# BatDuino1_0.net
KiCad netlist of a schematic drawn in EAGLE
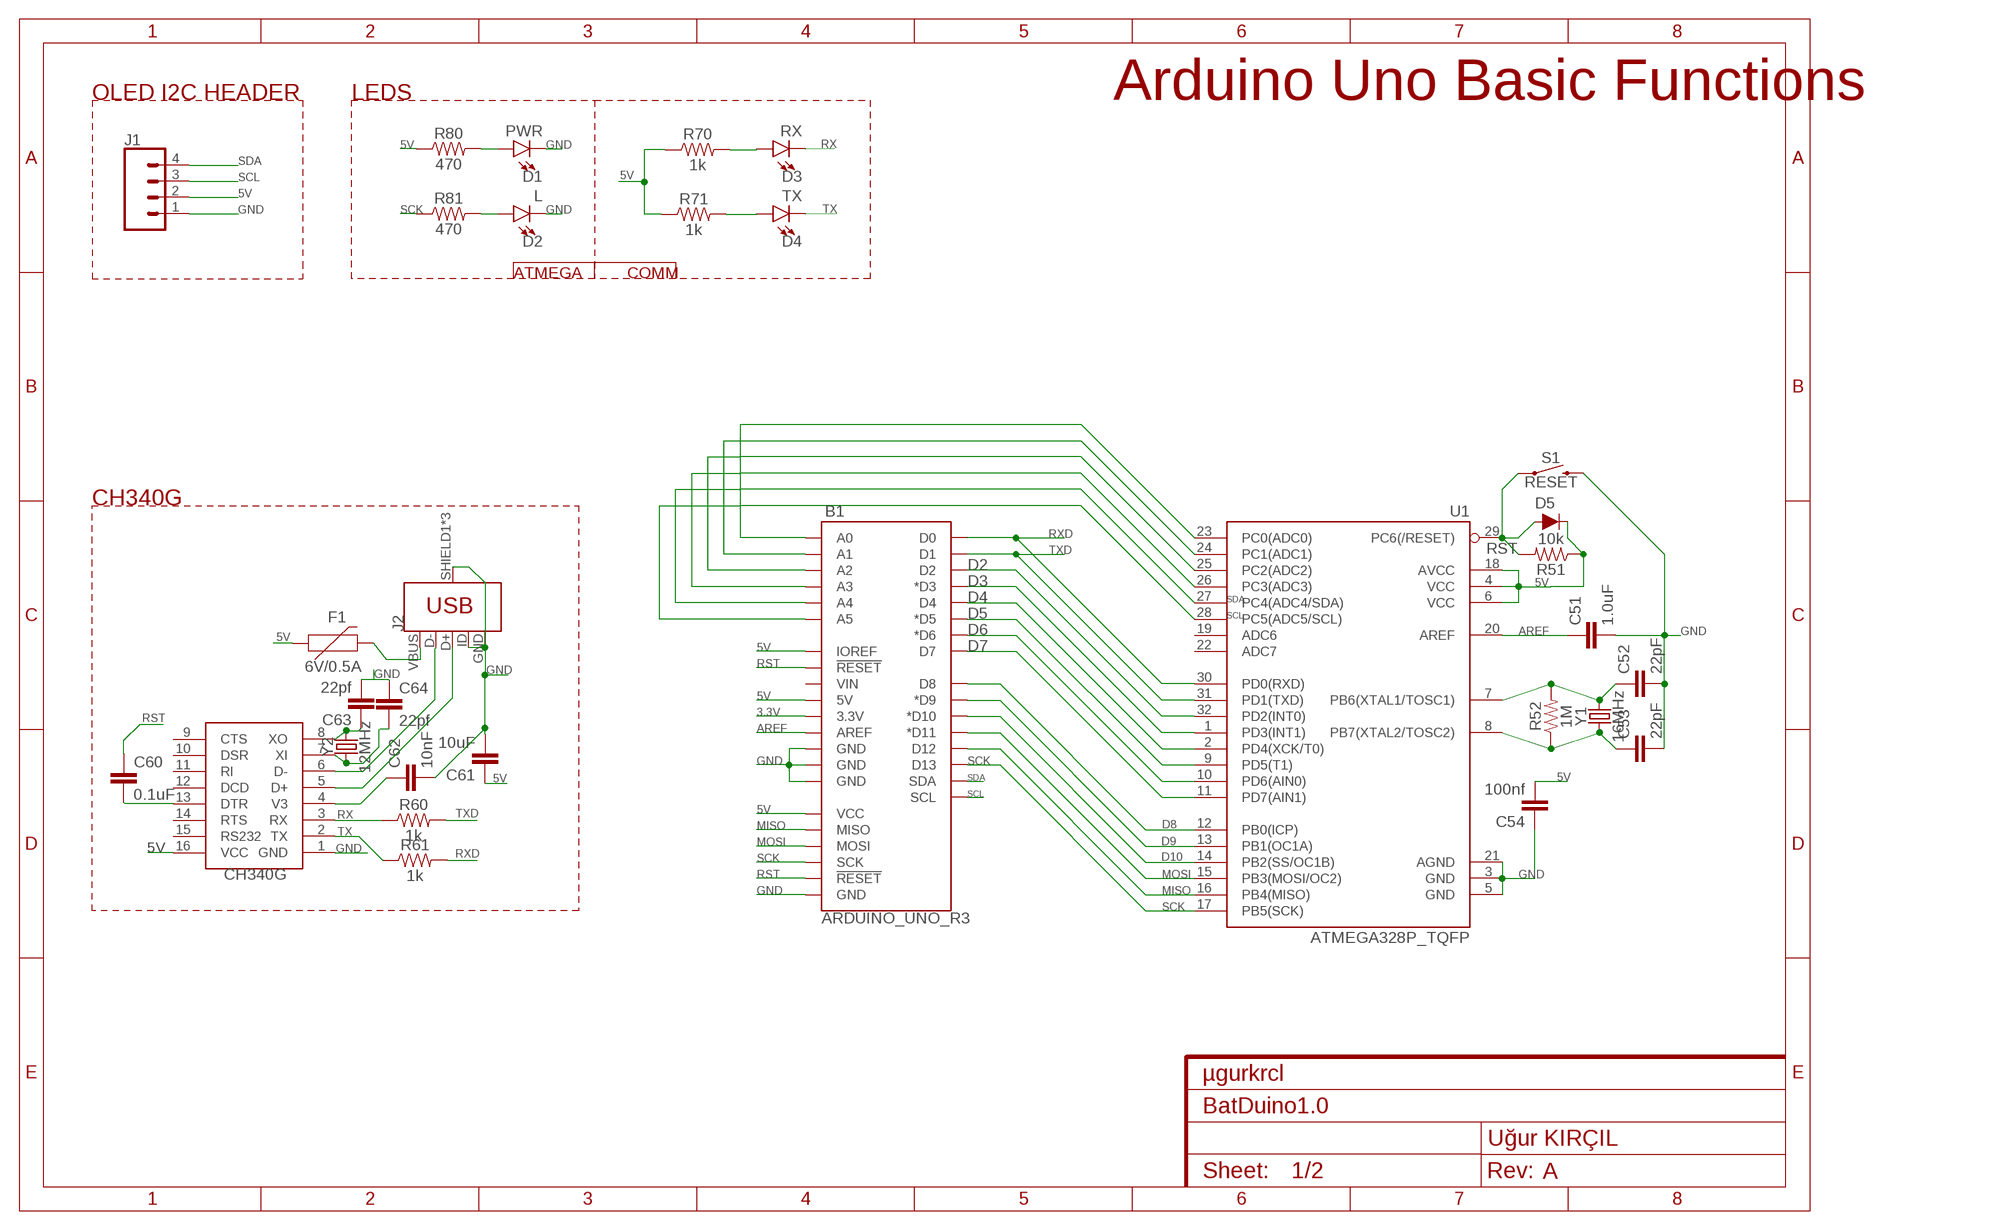
[diagram p0: schematic, sheet 1]
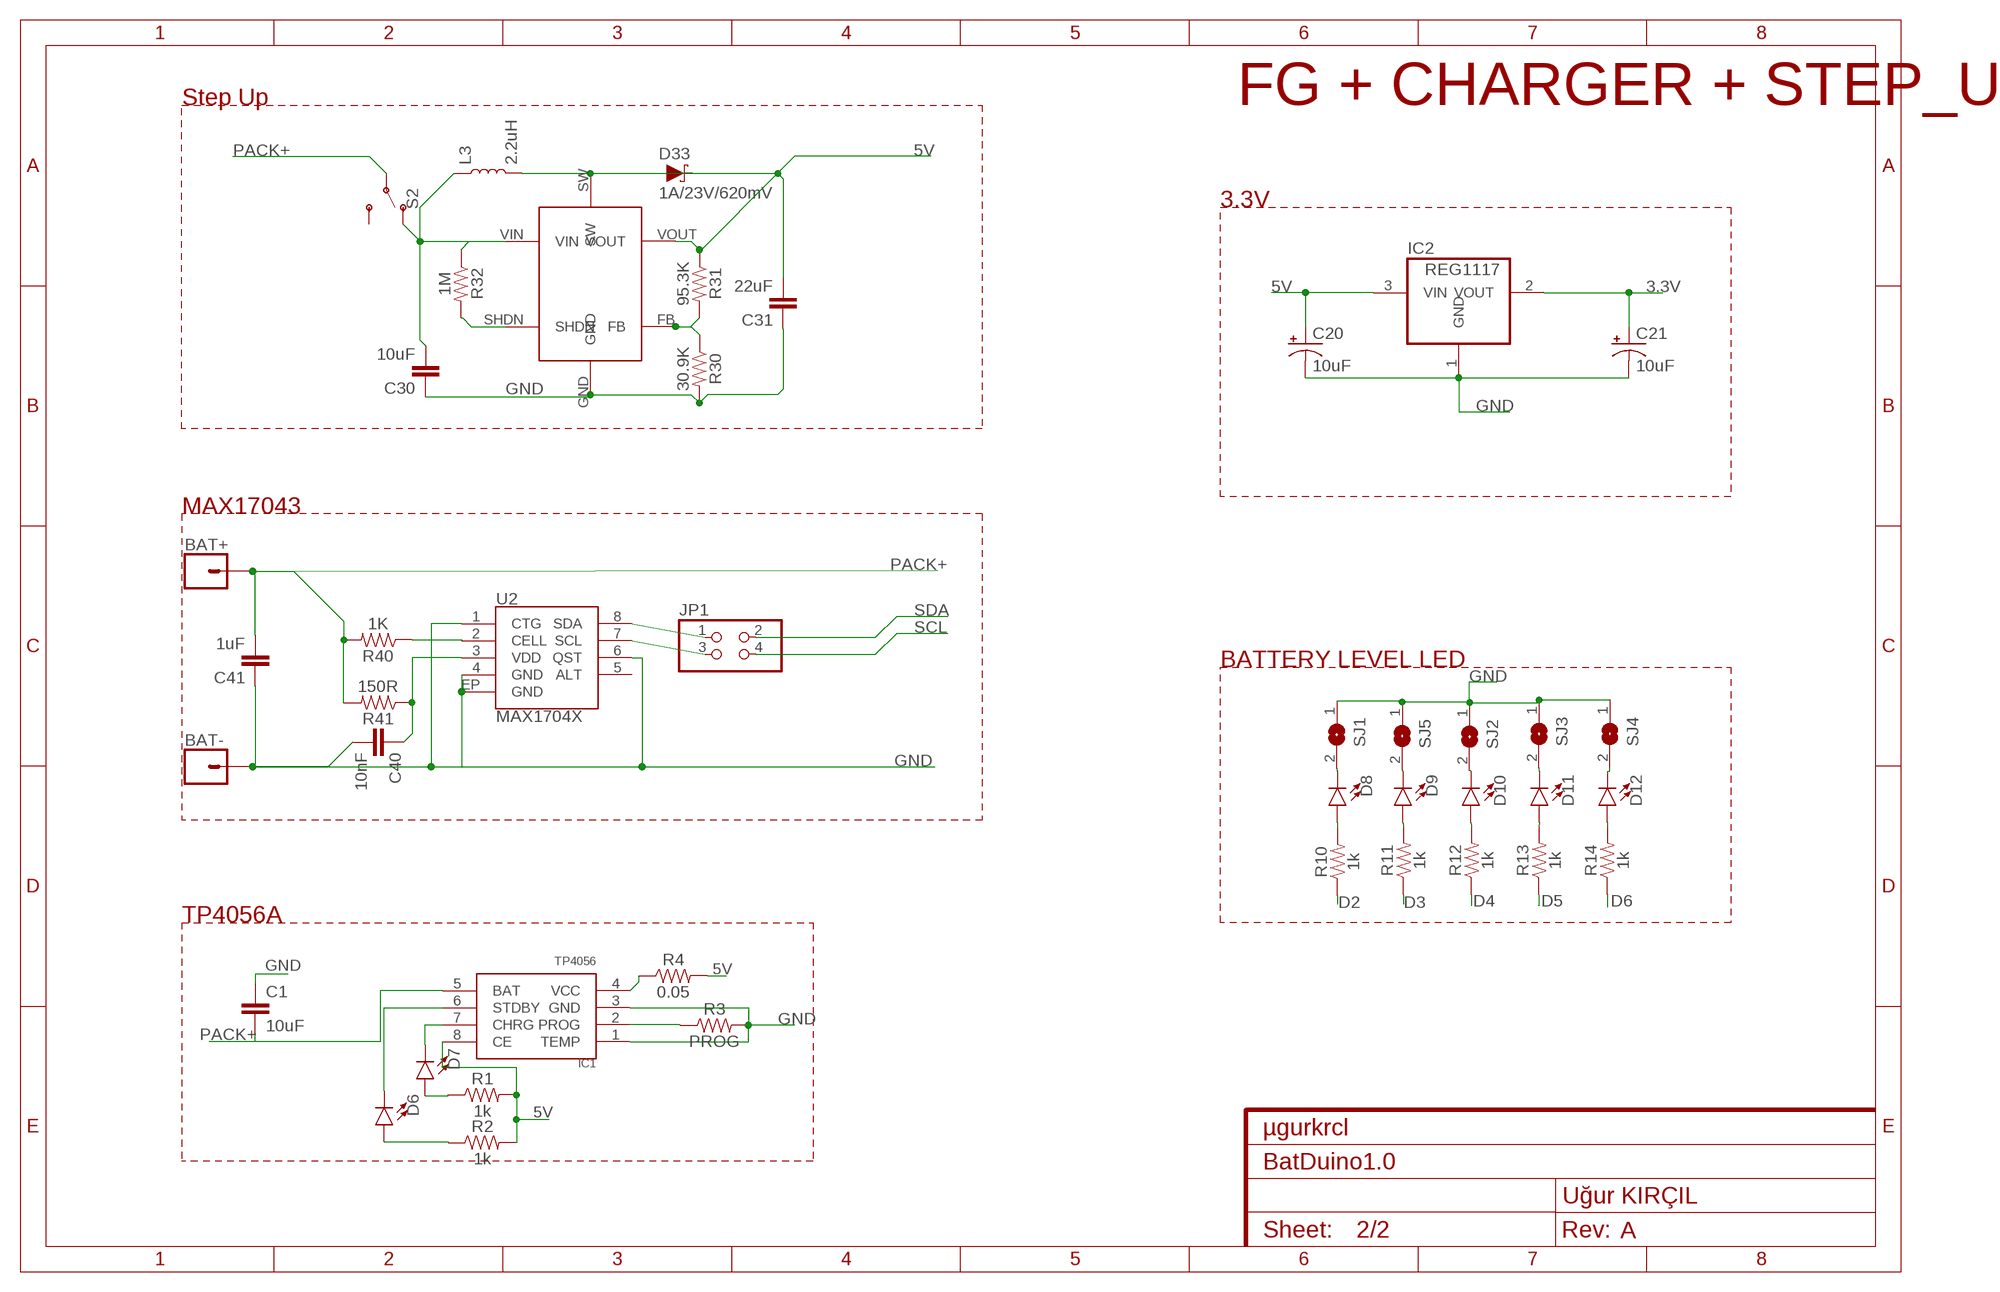
[diagram p1: schematic, sheet 2]

(export (version "E")
  (design (tool "Eeschema 10.0.6"))
  (components
    (comp (ref "B1")
      (value "ARDUINO_UNO_R3")
      (footprint "eagle-import:ARDUINO_R3")
      (libsource (lib "eagle-import") (part "ARDUINO_UNO_R3"))
    )
    (comp (ref "C51")
      (value "1.0uF")
      (footprint "eagle-import:0603")
      (libsource (lib "eagle-import") (part "1.0UF-0603-16V-10%"))
    )
    (comp (ref "C52")
      (value "22pF")
      (footprint "eagle-import:0603")
      (libsource (lib "eagle-import") (part "22PF-0603-50V-5%"))
    )
    (comp (ref "C53")
      (value "22pF")
      (footprint "eagle-import:0603")
      (libsource (lib "eagle-import") (part "22PF-0603-50V-5%"))
    )
    (comp (ref "C54")
      (value "100nf")
      (footprint "eagle-import:0603")
      (libsource (lib "eagle-import") (part "22PF-0603-50V-5%"))
    )
    (comp (ref "C60")
      (value "0.1uF")
      (footprint "eagle-import:0603")
      (libsource (lib "eagle-import") (part "0.1UF-0603-25V-5%"))
    )
    (comp (ref "C61")
      (value "10uF")
      (footprint "eagle-import:0603")
      (libsource (lib "eagle-import") (part "0.18UF-0603-10V-10%"))
    )
    (comp (ref "C62")
      (value "10nF")
      (footprint "eagle-import:0603")
      (libsource (lib "eagle-import") (part "0.18UF-0603-10V-10%"))
    )
    (comp (ref "C63")
      (value "22pf")
      (footprint "eagle-import:0603")
      (libsource (lib "eagle-import") (part "0.18UF-0603-10V-10%"))
    )
    (comp (ref "C64")
      (value "22pf")
      (footprint "eagle-import:0603")
      (libsource (lib "eagle-import") (part "0.18UF-0603-10V-10%"))
    )
    (comp (ref "D1")
      (value "PWR")
      (footprint "eagle-import:LED-0603")
      (libsource (lib "eagle-import") (part "LED-GREEN0603"))
    )
    (comp (ref "D2")
      (value "L")
      (footprint "eagle-import:LED-0603")
      (libsource (lib "eagle-import") (part "LED-GREEN0603"))
    )
    (comp (ref "D3")
      (value "RX")
      (footprint "eagle-import:LED-0603")
      (libsource (lib "eagle-import") (part "LED-GREEN0603"))
    )
    (comp (ref "D4")
      (value "TX")
      (footprint "eagle-import:LED-0603")
      (libsource (lib "eagle-import") (part "LED-GREEN0603"))
    )
    (comp (ref "D5")
      (value "DIODE-BAS16J")
      (footprint "eagle-import:SOD-323")
      (libsource (lib "eagle-import") (part "DIODE-BAS16J"))
    )
    (comp (ref "F1")
      (value "6V/0.5A")
      (footprint "eagle-import:1206")
      (libsource (lib "eagle-import") (part "PPTC_HALF-AMP"))
    )
    (comp (ref "J1")
      (value "CONN_04")
      (footprint "eagle-import:1X04")
      (libsource (lib "eagle-import") (part "CONN_04"))
    )
    (comp (ref "J2")
      (value "USB_MICRO-BREDUCED_PASTE")
      (footprint "eagle-import:USB-B-MICRO-SMD_RED_PASTE")
      (libsource (lib "eagle-import") (part "USB_MICRO-BREDUCED_PASTE"))
    )
    (comp (ref "R51")
      (value "10k")
      (footprint "eagle-import:0603")
      (libsource (lib "eagle-import") (part "10KOHM-0603-1/10W-1%"))
    )
    (comp (ref "R52")
      (value "1M")
      (footprint "eagle-import:0603")
      (libsource (lib "eagle-import") (part "1MOHM-0603-1/4W-5%"))
    )
    (comp (ref "R60")
      (value "1k")
      (footprint "eagle-import:0603")
      (libsource (lib "eagle-import") (part "1KOHM-0603-1/10W-1%"))
    )
    (comp (ref "R61")
      (value "1k")
      (footprint "eagle-import:0603")
      (libsource (lib "eagle-import") (part "1KOHM-0603-1/10W-1%"))
    )
    (comp (ref "R70")
      (value "1k")
      (footprint "eagle-import:0603")
      (libsource (lib "eagle-import") (part "1KOHM-0603-1/10W-1%"))
    )
    (comp (ref "R71")
      (value "1k")
      (footprint "eagle-import:0603")
      (libsource (lib "eagle-import") (part "1KOHM-0603-1/10W-1%"))
    )
    (comp (ref "R80")
      (value "470")
      (footprint "eagle-import:0603")
      (libsource (lib "eagle-import") (part "470OHM-0603-1/10W-1%"))
    )
    (comp (ref "R81")
      (value "470")
      (footprint "eagle-import:0603")
      (libsource (lib "eagle-import") (part "470OHM-0603-1/10W-1%"))
    )
    (comp (ref "S1")
      (value "RESET")
      (footprint "eagle-import:TACTILE_SWITCH_PTH_6.0MM")
      (libsource (lib "eagle-import") (part "MOMENTARY-SWITCH-SPST-PTH-6.0MM"))
    )
    (comp (ref "U$1")
      (value "CH340G")
      (footprint "eagle-import:SOIC16")
      (libsource (lib "eagle-import") (part "CH340G"))
    )
    (comp (ref "U1")
      (value "ATMEGA328P_TQFP")
      (footprint "eagle-import:TQFP32-08")
      (libsource (lib "eagle-import") (part "ATMEGA328P_TQFP"))
    )
    (comp (ref "Y1")
      (value "16MHz")
      (footprint "eagle-import:HC49US")
      (libsource (lib "eagle-import") (part "CRYSTAL-16MHZPTH-HC49US"))
    )
    (comp (ref "Y2")
      (value "12MHz")
      (footprint "eagle-import:HC49US")
      (libsource (lib "eagle-import") (part "CRYSTAL-16MHZPTH-HC49US"))
    )
    (comp (ref "BAT+")
      (value "CONN_01")
      (footprint "eagle-import:1X01")
      (libsource (lib "eagle-import") (part "CONN_01"))
    )
    (comp (ref "BAT-")
      (value "CONN_01")
      (footprint "eagle-import:1X01")
      (libsource (lib "eagle-import") (part "CONN_01"))
    )
    (comp (ref "C1")
      (value "10uF")
      (footprint "eagle-import:0603")
      (libsource (lib "eagle-import") (part "10UF-0603-6.3V-20%"))
    )
    (comp (ref "C20")
      (value "10uF")
      (footprint "eagle-import:EIA3528")
      (libsource (lib "eagle-import") (part "10UF-POLAR-EIA3528-20V-10%(TANT)"))
    )
    (comp (ref "C21")
      (value "10uF")
      (footprint "eagle-import:EIA3528")
      (libsource (lib "eagle-import") (part "10UF-POLAR-EIA3528-20V-10%(TANT)"))
    )
    (comp (ref "C30")
      (value "10uF")
      (footprint "eagle-import:0603")
      (libsource (lib "eagle-import") (part "0.1UF-0603-25V-(+80/-20%)"))
    )
    (comp (ref "C31")
      (value "22uF")
      (footprint "eagle-import:0603")
      (libsource (lib "eagle-import") (part "0.1UF-0603-25V-(+80/-20%)"))
    )
    (comp (ref "C40")
      (value "10nF")
      (footprint "eagle-import:0603")
      (libsource (lib "eagle-import") (part "0.1UF-0603-25V-(+80/-20%)"))
    )
    (comp (ref "C41")
      (value "1uF")
      (footprint "eagle-import:0603")
      (libsource (lib "eagle-import") (part "0.1UF-0603-25V-(+80/-20%)"))
    )
    (comp (ref "D6")
      (value "LED0603")
      (footprint "eagle-import:LED-0603")
      (libsource (lib "eagle-import") (part "LED0603"))
    )
    (comp (ref "D7")
      (value "LED0603")
      (footprint "eagle-import:LED-0603")
      (libsource (lib "eagle-import") (part "LED0603"))
    )
    (comp (ref "D8")
      (value "LED0603")
      (footprint "eagle-import:LED-0603")
      (libsource (lib "eagle-import") (part "LED0603"))
    )
    (comp (ref "D9")
      (value "LED0603")
      (footprint "eagle-import:LED-0603")
      (libsource (lib "eagle-import") (part "LED0603"))
    )
    (comp (ref "D10")
      (value "LED0603")
      (footprint "eagle-import:LED-0603")
      (libsource (lib "eagle-import") (part "LED0603"))
    )
    (comp (ref "D11")
      (value "LED0603")
      (footprint "eagle-import:LED-0603")
      (libsource (lib "eagle-import") (part "LED0603"))
    )
    (comp (ref "D12")
      (value "LED0603")
      (footprint "eagle-import:LED-0603")
      (libsource (lib "eagle-import") (part "LED0603"))
    )
    (comp (ref "D33")
      (value "1A/23V/620mV")
      (footprint "eagle-import:SOD-323")
      (libsource (lib "eagle-import") (part "DIODE-SCHOTTKY-BAT20J"))
    )
    (comp (ref "IC1")
      (value "TP4056")
      (footprint "eagle-import:SOP-8")
      (libsource (lib "eagle-import") (part "TP4056"))
    )
    (comp (ref "IC2")
      (value "REG1117")
      (footprint "eagle-import:SOT223")
      (libsource (lib "eagle-import") (part "REG1117"))
    )
    (comp (ref "JP1")
      (value "PINHD-2X2")
      (footprint "eagle-import:2X02")
      (libsource (lib "eagle-import") (part "PINHD-2X2"))
    )
    (comp (ref "L3")
      (value "2.2uH")
      (footprint "eagle-import:INDUCTOR_4.7UH")
      (libsource (lib "eagle-import") (part "INDUCTOR-CDRH-4.7UH"))
    )
    (comp (ref "R1")
      (value "1k")
      (footprint "eagle-import:0603")
      (libsource (lib "eagle-import") (part "1KOHM-0603-1/10W-1%"))
    )
    (comp (ref "R2")
      (value "1k")
      (footprint "eagle-import:0603")
      (libsource (lib "eagle-import") (part "1KOHM-0603-1/10W-1%"))
    )
    (comp (ref "R3")
      (value "PROG")
      (footprint "eagle-import:AXIAL-0.3")
      (libsource (lib "eagle-import") (part "1KOHM-HORIZ-1/4W-1%"))
    )
    (comp (ref "R4")
      (value "0.05")
      (footprint "eagle-import:0603")
      (libsource (lib "eagle-import") (part "0.05OHM-0603-1/5W-1%"))
    )
    (comp (ref "R10")
      (value "1k")
      (footprint "eagle-import:0603")
      (libsource (lib "eagle-import") (part "1KOHM-0603-1/10W-1%"))
    )
    (comp (ref "R11")
      (value "1k")
      (footprint "eagle-import:0603")
      (libsource (lib "eagle-import") (part "1KOHM-0603-1/10W-1%"))
    )
    (comp (ref "R12")
      (value "1k")
      (footprint "eagle-import:0603")
      (libsource (lib "eagle-import") (part "1KOHM-0603-1/10W-1%"))
    )
    (comp (ref "R13")
      (value "1k")
      (footprint "eagle-import:0603")
      (libsource (lib "eagle-import") (part "1KOHM-0603-1/10W-1%"))
    )
    (comp (ref "R14")
      (value "1k")
      (footprint "eagle-import:0603")
      (libsource (lib "eagle-import") (part "1KOHM-0603-1/10W-1%"))
    )
    (comp (ref "R30")
      (value "30.9K")
      (footprint "eagle-import:0603")
      (libsource (lib "eagle-import") (part "0.05OHM-0603-1/5W-1%"))
    )
    (comp (ref "R31")
      (value "95.3K")
      (footprint "eagle-import:0603")
      (libsource (lib "eagle-import") (part "0.05OHM-0603-1/5W-1%"))
    )
    (comp (ref "R32")
      (value "1M")
      (footprint "eagle-import:0603")
      (libsource (lib "eagle-import") (part "0.05OHM-0603-1/5W-1%"))
    )
    (comp (ref "R40")
      (value "1K")
      (footprint "eagle-import:0603")
      (libsource (lib "eagle-import") (part "0.05OHM-0603-1/5W-1%"))
    )
    (comp (ref "R41")
      (value "150R")
      (footprint "eagle-import:0603")
      (libsource (lib "eagle-import") (part "0.05OHM-0603-1/5W-1%"))
    )
    (comp (ref "S2")
      (value "SWITCH-SPDT-SMD-RIGHT-ANGLE")
      (footprint "eagle-import:SWITCH_SPST_SMD_A")
      (libsource (lib "eagle-import") (part "SWITCH-SPDT-SMD-RIGHT-ANGLE"))
    )
    (comp (ref "SJ1") (value "SJ") (footprint "eagle-import:SJ") (libsource (lib "eagle-import") (part "SJ")))
    (comp (ref "SJ2") (value "SJ") (footprint "eagle-import:SJ") (libsource (lib "eagle-import") (part "SJ")))
    (comp (ref "SJ3") (value "SJ") (footprint "eagle-import:SJ") (libsource (lib "eagle-import") (part "SJ")))
    (comp (ref "SJ4") (value "SJ") (footprint "eagle-import:SJ") (libsource (lib "eagle-import") (part "SJ")))
    (comp (ref "SJ5") (value "SJ") (footprint "eagle-import:SJ") (libsource (lib "eagle-import") (part "SJ")))
    (comp (ref "U$2")
      (value "XR1151")
      (footprint "eagle-import:SOT23-6")
      (libsource (lib "eagle-import") (part "XR1151"))
    )
    (comp (ref "U2")
      (value "MAX1704X")
      (footprint "eagle-import:TDFN-8")
      (libsource (lib "eagle-import") (part "MAX1704X"))
    )
  )
  (nets
    (net (code "1") (name "3.3V") (class "Default")
      (node (ref "B1") (pin "3.3V") (pinfunction "3.3V_3.3V") (pintype "bidirectional"))
      (node (ref "C21") (pin "A") (pinfunction "+_A") (pintype "passive"))
      (node (ref "IC2") (pin "2") (pinfunction "VOUT_2") (pintype "output"))
    )
    (net (code "2") (name "5V") (class "Default")
      (node (ref "B1") (pin "5V") (pinfunction "5V_5V") (pintype "bidirectional"))
      (node (ref "B1") (pin "IOREF") (pinfunction "IOREF_IOREF") (pintype "bidirectional"))
      (node (ref "B1") (pin "VCC") (pinfunction "VCC_VCC") (pintype "bidirectional"))
      (node (ref "C20") (pin "A") (pinfunction "+_A") (pintype "passive"))
      (node (ref "C31") (pin "2") (pinfunction "2_2") (pintype "passive"))
      (node (ref "C54") (pin "2") (pinfunction "2_2") (pintype "passive"))
      (node (ref "C61") (pin "1") (pinfunction "1_1") (pintype "passive"))
      (node (ref "D33") (pin "A") (pinfunction "A_A") (pintype "passive"))
      (node (ref "D5") (pin "C") (pinfunction "C_C") (pintype "passive"))
      (node (ref "F1") (pin "1") (pinfunction "1_1") (pintype "bidirectional"))
      (node (ref "IC1") (pin "8") (pinfunction "CE_8") (pintype "bidirectional"))
      (node (ref "IC2") (pin "3") (pinfunction "VIN_3") (pintype "input"))
      (node (ref "J1") (pin "2") (pinfunction "2_2") (pintype "passive"))
      (node (ref "R1") (pin "2") (pinfunction "2_2") (pintype "passive"))
      (node (ref "R2") (pin "2") (pinfunction "2_2") (pintype "passive"))
      (node (ref "R31") (pin "1") (pinfunction "1_1") (pintype "passive"))
      (node (ref "R4") (pin "2") (pinfunction "2_2") (pintype "passive"))
      (node (ref "R51") (pin "1") (pinfunction "1_1") (pintype "passive"))
      (node (ref "R70") (pin "1") (pinfunction "1_1") (pintype "passive"))
      (node (ref "R71") (pin "1") (pinfunction "1_1") (pintype "passive"))
      (node (ref "R80") (pin "1") (pinfunction "1_1") (pintype "passive"))
      (node (ref "U$1") (pin "16") (pinfunction "VCC_16") (pintype "bidirectional"))
      (node (ref "U$2") (pin "VOUT") (pinfunction "VOUT_VOUT") (pintype "power_in"))
      (node (ref "U1") (pin "18") (pinfunction "AVCC_18") (pintype "bidirectional"))
      (node (ref "U1") (pin "4") (pinfunction "VCC_4") (pintype "bidirectional"))
      (node (ref "U1") (pin "6") (pinfunction "VCC_6") (pintype "bidirectional"))
    )
    (net (code "3") (name "AREF") (class "Default")
      (node (ref "B1") (pin "AREF") (pinfunction "AREF_AREF") (pintype "bidirectional"))
      (node (ref "C51") (pin "1") (pinfunction "1_1") (pintype "passive"))
      (node (ref "U1") (pin "20") (pinfunction "AREF_20") (pintype "bidirectional"))
    )
    (net (code "4") (name "D2") (class "Default")
      (node (ref "B1") (pin "D2") (pinfunction "D2_D2") (pintype "bidirectional"))
      (node (ref "R10") (pin "1") (pinfunction "1_1") (pintype "passive"))
      (node (ref "U1") (pin "32") (pinfunction "PD2(INT0)_32") (pintype "bidirectional"))
    )
    (net (code "5") (name "D3") (class "Default")
      (node (ref "B1") (pin "D3") (pinfunction "*D3_D3") (pintype "bidirectional"))
      (node (ref "R11") (pin "1") (pinfunction "1_1") (pintype "passive"))
      (node (ref "U1") (pin "1") (pinfunction "PD3(INT1)_1") (pintype "bidirectional"))
    )
    (net (code "6") (name "D4") (class "Default")
      (node (ref "B1") (pin "D4") (pinfunction "D4_D4") (pintype "bidirectional"))
      (node (ref "R12") (pin "1") (pinfunction "1_1") (pintype "passive"))
      (node (ref "U1") (pin "2") (pinfunction "PD4(XCK/T0)_2") (pintype "bidirectional"))
    )
    (net (code "7") (name "D5") (class "Default")
      (node (ref "B1") (pin "D5") (pinfunction "*D5_D5") (pintype "bidirectional"))
      (node (ref "R13") (pin "1") (pinfunction "1_1") (pintype "passive"))
      (node (ref "U1") (pin "9") (pinfunction "PD5(T1)_9") (pintype "bidirectional"))
    )
    (net (code "8") (name "D6") (class "Default")
      (node (ref "B1") (pin "D6") (pinfunction "*D6_D6") (pintype "bidirectional"))
      (node (ref "R14") (pin "1") (pinfunction "1_1") (pintype "passive"))
      (node (ref "U1") (pin "10") (pinfunction "PD6(AIN0)_10") (pintype "bidirectional"))
    )
    (net (code "9") (name "D7") (class "Default")
      (node (ref "B1") (pin "D7") (pinfunction "D7_D7") (pintype "bidirectional"))
      (node (ref "U1") (pin "11") (pinfunction "PD7(AIN1)_11") (pintype "bidirectional"))
    )
    (net (code "10") (name "D8") (class "Default")
      (node (ref "B1") (pin "D8") (pinfunction "D8_D8") (pintype "bidirectional"))
      (node (ref "U1") (pin "12") (pinfunction "PB0(ICP)_12") (pintype "bidirectional"))
    )
    (net (code "11") (name "D9") (class "Default")
      (node (ref "B1") (pin "D9") (pinfunction "*D9_D9") (pintype "bidirectional"))
      (node (ref "U1") (pin "13") (pinfunction "PB1(OC1A)_13") (pintype "bidirectional"))
    )
    (net (code "12") (name "D10") (class "Default")
      (node (ref "B1") (pin "D10") (pinfunction "*D10_D10") (pintype "bidirectional"))
      (node (ref "U1") (pin "14") (pinfunction "PB2(SS/OC1B)_14") (pintype "bidirectional"))
    )
    (net (code "13") (name "GND") (class "Default")
      (node (ref "B1") (pin "GND@1") (pinfunction "GND_GND@1") (pintype "bidirectional"))
      (node (ref "B1") (pin "GND@2") (pinfunction "GND_GND@2") (pintype "bidirectional"))
      (node (ref "B1") (pin "GND@3") (pinfunction "GND_GND@3") (pintype "bidirectional"))
      (node (ref "B1") (pin "GND@4") (pinfunction "GND_GND@4") (pintype "bidirectional"))
      (node (ref "BAT-") (pin "1") (pinfunction "1_1") (pintype "passive"))
      (node (ref "C1") (pin "1") (pinfunction "1_1") (pintype "passive"))
      (node (ref "C20") (pin "C") (pinfunction "-_C") (pintype "passive"))
      (node (ref "C21") (pin "C") (pinfunction "-_C") (pintype "passive"))
      (node (ref "C30") (pin "1") (pinfunction "1_1") (pintype "passive"))
      (node (ref "C31") (pin "1") (pinfunction "1_1") (pintype "passive"))
      (node (ref "C40") (pin "2") (pinfunction "2_2") (pintype "passive"))
      (node (ref "C41") (pin "1") (pinfunction "1_1") (pintype "passive"))
      (node (ref "C51") (pin "2") (pinfunction "2_2") (pintype "passive"))
      (node (ref "C52") (pin "2") (pinfunction "2_2") (pintype "passive"))
      (node (ref "C53") (pin "2") (pinfunction "2_2") (pintype "passive"))
      (node (ref "C54") (pin "1") (pinfunction "1_1") (pintype "passive"))
      (node (ref "C61") (pin "2") (pinfunction "2_2") (pintype "passive"))
      (node (ref "C62") (pin "2") (pinfunction "2_2") (pintype "passive"))
      (node (ref "D1") (pin "C") (pinfunction "C_C") (pintype "passive"))
      (node (ref "D2") (pin "C") (pinfunction "C_C") (pintype "passive"))
      (node (ref "IC1") (pin "1") (pinfunction "TEMP_1") (pintype "bidirectional"))
      (node (ref "IC1") (pin "3") (pinfunction "GND_3") (pintype "bidirectional"))
      (node (ref "IC2") (pin "1") (pinfunction "GND_1") (pintype "power_in"))
      (node (ref "J1") (pin "1") (pinfunction "1_1") (pintype "passive"))
      (node (ref "J2") (pin "GND") (pinfunction "GND_GND") (pintype "power_in"))
      (node (ref "J2") (pin "ID") (pinfunction "ID_ID") (pintype "bidirectional"))
      (node (ref "J2") (pin "SHIELD1") (pinfunction "SHIELD_SHIELD1") (pintype "bidirectional"))
      (node (ref "J2") (pin "SHIELD2") (pinfunction "SHIELD_SHIELD2") (pintype "bidirectional"))
      (node (ref "J2") (pin "SHIELD3") (pinfunction "SHIELD_SHIELD3") (pintype "bidirectional"))
      (node (ref "R3") (pin "P$2") (pinfunction "2_P$2") (pintype "passive"))
      (node (ref "R30") (pin "2") (pinfunction "2_2") (pintype "passive"))
      (node (ref "S1") (pin "3") (pinfunction "2_3") (pintype "passive"))
      (node (ref "SJ1") (pin "1") (pinfunction "1_1") (pintype "passive"))
      (node (ref "SJ2") (pin "1") (pinfunction "1_1") (pintype "passive"))
      (node (ref "SJ3") (pin "1") (pinfunction "1_1") (pintype "passive"))
      (node (ref "SJ4") (pin "1") (pinfunction "1_1") (pintype "passive"))
      (node (ref "SJ5") (pin "1") (pinfunction "1_1") (pintype "passive"))
      (node (ref "U$1") (pin "1") (pinfunction "GND_1") (pintype "bidirectional"))
      (node (ref "U$2") (pin "GND") (pinfunction "GND_GND") (pintype "power_in"))
      (node (ref "U1") (pin "21") (pinfunction "AGND_21") (pintype "bidirectional"))
      (node (ref "U1") (pin "3") (pinfunction "GND_3") (pintype "bidirectional"))
      (node (ref "U1") (pin "5") (pinfunction "GND_5") (pintype "bidirectional"))
      (node (ref "U2") (pin "1") (pinfunction "CTG_1") (pintype "bidirectional"))
      (node (ref "U2") (pin "4") (pinfunction "GND_4") (pintype "bidirectional"))
      (node (ref "U2") (pin "6") (pinfunction "QST_6") (pintype "bidirectional"))
      (node (ref "U2") (pin "EP") (pinfunction "GND_EP") (pintype "bidirectional"))
    )
    (net (code "14") (name "MISO") (class "Default")
      (node (ref "B1") (pin "D12") (pinfunction "D12_D12") (pintype "bidirectional"))
      (node (ref "B1") (pin "MISO") (pinfunction "MISO_MISO") (pintype "bidirectional"))
      (node (ref "U1") (pin "16") (pinfunction "PB4(MISO)_16") (pintype "bidirectional"))
    )
    (net (code "15") (name "MOSI") (class "Default")
      (node (ref "B1") (pin "D11") (pinfunction "*D11_D11") (pintype "bidirectional"))
      (node (ref "B1") (pin "MOSI") (pinfunction "MOSI_MOSI") (pintype "bidirectional"))
      (node (ref "U1") (pin "15") (pinfunction "PB3(MOSI/OC2)_15") (pintype "bidirectional"))
    )
    (net (code "16") (name "Net-(C63-Pad2)") (class "Default")
      (node (ref "C63") (pin "2") (pinfunction "2_2") (pintype "passive"))
      (node (ref "C64") (pin "1") (pinfunction "1_1") (pintype "passive"))
    )
    (net (code "17") (name "Net-(D1-PadA)") (class "Default")
      (node (ref "D1") (pin "A") (pinfunction "A_A") (pintype "passive"))
      (node (ref "R80") (pin "2") (pinfunction "2_2") (pintype "passive"))
    )
    (net (code "18") (name "Net-(D2-PadA)") (class "Default")
      (node (ref "D2") (pin "A") (pinfunction "A_A") (pintype "passive"))
      (node (ref "R81") (pin "2") (pinfunction "2_2") (pintype "passive"))
    )
    (net (code "19") (name "Net-(D3-PadA)") (class "Default")
      (node (ref "D3") (pin "A") (pinfunction "A_A") (pintype "passive"))
      (node (ref "R70") (pin "2") (pinfunction "2_2") (pintype "passive"))
    )
    (net (code "20") (name "Net-(D4-PadA)") (class "Default")
      (node (ref "D4") (pin "A") (pinfunction "A_A") (pintype "passive"))
      (node (ref "R71") (pin "2") (pinfunction "2_2") (pintype "passive"))
    )
    (net (code "21") (name "Net-(D6-PadA)") (class "Default")
      (node (ref "D6") (pin "A") (pinfunction "A_A") (pintype "passive"))
      (node (ref "R2") (pin "1") (pinfunction "1_1") (pintype "passive"))
    )
    (net (code "22") (name "Net-(D7-PadA)") (class "Default")
      (node (ref "D7") (pin "A") (pinfunction "A_A") (pintype "passive"))
      (node (ref "R1") (pin "1") (pinfunction "1_1") (pintype "passive"))
    )
    (net (code "23") (name "Net-(D8-PadA)") (class "Default")
      (node (ref "D8") (pin "A") (pinfunction "A_A") (pintype "passive"))
      (node (ref "R10") (pin "2") (pinfunction "2_2") (pintype "passive"))
    )
    (net (code "24") (name "Net-(D8-PadC)") (class "Default")
      (node (ref "D8") (pin "C") (pinfunction "C_C") (pintype "passive"))
      (node (ref "SJ1") (pin "2") (pinfunction "2_2") (pintype "passive"))
    )
    (net (code "25") (name "Net-(D9-PadA)") (class "Default")
      (node (ref "D9") (pin "A") (pinfunction "A_A") (pintype "passive"))
      (node (ref "R11") (pin "2") (pinfunction "2_2") (pintype "passive"))
    )
    (net (code "26") (name "Net-(D9-PadC)") (class "Default")
      (node (ref "D9") (pin "C") (pinfunction "C_C") (pintype "passive"))
      (node (ref "SJ5") (pin "2") (pinfunction "2_2") (pintype "passive"))
    )
    (net (code "27") (name "Net-(D10-PadA)") (class "Default")
      (node (ref "D10") (pin "A") (pinfunction "A_A") (pintype "passive"))
      (node (ref "R12") (pin "2") (pinfunction "2_2") (pintype "passive"))
    )
    (net (code "28") (name "Net-(D10-PadC)") (class "Default")
      (node (ref "D10") (pin "C") (pinfunction "C_C") (pintype "passive"))
      (node (ref "SJ2") (pin "2") (pinfunction "2_2") (pintype "passive"))
    )
    (net (code "29") (name "Net-(D11-PadA)") (class "Default")
      (node (ref "D11") (pin "A") (pinfunction "A_A") (pintype "passive"))
      (node (ref "R13") (pin "2") (pinfunction "2_2") (pintype "passive"))
    )
    (net (code "30") (name "Net-(D11-PadC)") (class "Default")
      (node (ref "D11") (pin "C") (pinfunction "C_C") (pintype "passive"))
      (node (ref "SJ3") (pin "2") (pinfunction "2_2") (pintype "passive"))
    )
    (net (code "31") (name "Net-(D12-PadA)") (class "Default")
      (node (ref "D12") (pin "A") (pinfunction "A_A") (pintype "passive"))
      (node (ref "R14") (pin "2") (pinfunction "2_2") (pintype "passive"))
    )
    (net (code "32") (name "Net-(D12-PadC)") (class "Default")
      (node (ref "D12") (pin "C") (pinfunction "C_C") (pintype "passive"))
      (node (ref "SJ4") (pin "2") (pinfunction "2_2") (pintype "passive"))
    )
    (net (code "33") (name "Net-(F1-Pad2)") (class "Default")
      (node (ref "F1") (pin "2") (pinfunction "2_2") (pintype "bidirectional"))
      (node (ref "J2") (pin "VBUS") (pinfunction "VBUS_VBUS") (pintype "power_in"))
    )
    (net (code "34") (name "Net-(IC1-CHRG)") (class "Default")
      (node (ref "D7") (pin "C") (pinfunction "C_C") (pintype "passive"))
      (node (ref "IC1") (pin "7") (pinfunction "CHRG_7") (pintype "bidirectional"))
    )
    (net (code "35") (name "Net-(IC1-PROG)") (class "Default")
      (node (ref "IC1") (pin "2") (pinfunction "PROG_2") (pintype "bidirectional"))
      (node (ref "R3") (pin "P$1") (pinfunction "1_P$1") (pintype "passive"))
    )
    (net (code "36") (name "Net-(IC1-STDBY)") (class "Default")
      (node (ref "D6") (pin "C") (pinfunction "C_C") (pintype "passive"))
      (node (ref "IC1") (pin "6") (pinfunction "STDBY_6") (pintype "bidirectional"))
    )
    (net (code "37") (name "Net-(IC1-VCC)") (class "Default")
      (node (ref "IC1") (pin "4") (pinfunction "VCC_4") (pintype "bidirectional"))
      (node (ref "R4") (pin "1") (pinfunction "1_1") (pintype "passive"))
    )
    (net (code "38") (name "Net-(L3-1)") (class "Default")
      (node (ref "C30") (pin "2") (pinfunction "2_2") (pintype "passive"))
      (node (ref "L3") (pin "P$1") (pinfunction "1_P$1") (pintype "passive"))
      (node (ref "R32") (pin "1") (pinfunction "1_1") (pintype "passive"))
      (node (ref "S2") (pin "1") (pinfunction "O_1") (pintype "passive"))
      (node (ref "U$2") (pin "VIN") (pinfunction "VIN_VIN") (pintype "power_in"))
    )
    (net (code "39") (name "Net-(L3-2)") (class "Default")
      (node (ref "D33") (pin "C") (pinfunction "C_C") (pintype "passive"))
      (node (ref "L3") (pin "P$2") (pinfunction "2_P$2") (pintype "passive"))
      (node (ref "U$2") (pin "SW") (pinfunction "SW_SW") (pintype "power_in"))
    )
    (net (code "40") (name "Net-(R30-Pad1)") (class "Default")
      (node (ref "R30") (pin "1") (pinfunction "1_1") (pintype "passive"))
      (node (ref "R31") (pin "2") (pinfunction "2_2") (pintype "passive"))
      (node (ref "U$2") (pin "FB") (pinfunction "FB_FB") (pintype "power_in"))
    )
    (net (code "41") (name "Net-(R32-Pad2)") (class "Default")
      (node (ref "R32") (pin "2") (pinfunction "2_2") (pintype "passive"))
      (node (ref "U$2") (pin "SHDN") (pinfunction "SHDN_SHDN") (pintype "power_in"))
    )
    (net (code "42") (name "Net-(U$1-D+)") (class "Default")
      (node (ref "J2") (pin "D+") (pinfunction "D+_D+") (pintype "bidirectional"))
      (node (ref "U$1") (pin "5") (pinfunction "D+_5") (pintype "bidirectional"))
    )
    (net (code "43") (name "Net-(U$1-D-)") (class "Default")
      (node (ref "J2") (pin "D-") (pinfunction "D-_D-") (pintype "bidirectional"))
      (node (ref "U$1") (pin "6") (pinfunction "D-_6") (pintype "bidirectional"))
    )
    (net (code "44") (name "Net-(U$1-DTR)") (class "Default")
      (node (ref "C60") (pin "2") (pinfunction "2_2") (pintype "passive"))
      (node (ref "U$1") (pin "13") (pinfunction "DTR_13") (pintype "bidirectional"))
    )
    (net (code "45") (name "Net-(U$1-V3)") (class "Default")
      (node (ref "C62") (pin "1") (pinfunction "1_1") (pintype "passive"))
      (node (ref "U$1") (pin "4") (pinfunction "V3_4") (pintype "bidirectional"))
    )
    (net (code "46") (name "Net-(U$1-XI)") (class "Default")
      (node (ref "C64") (pin "2") (pinfunction "2_2") (pintype "passive"))
      (node (ref "U$1") (pin "7") (pinfunction "XI_7") (pintype "bidirectional"))
      (node (ref "Y2") (pin "1") (pinfunction "1_1") (pintype "passive"))
    )
    (net (code "47") (name "Net-(U$1-XO)") (class "Default")
      (node (ref "C63") (pin "1") (pinfunction "1_1") (pintype "passive"))
      (node (ref "U$1") (pin "8") (pinfunction "XO_8") (pintype "bidirectional"))
      (node (ref "Y2") (pin "2") (pinfunction "2_2") (pintype "passive"))
    )
    (net (code "48") (name "Net-(U1-PB6(XTAL1{slash}TOSC1))") (class "Default")
      (node (ref "C52") (pin "1") (pinfunction "1_1") (pintype "passive"))
      (node (ref "R52") (pin "2") (pinfunction "2_2") (pintype "passive"))
      (node (ref "U1") (pin "7") (pinfunction "PB6(XTAL1/TOSC1)_7") (pintype "bidirectional"))
      (node (ref "Y1") (pin "2") (pinfunction "2_2") (pintype "passive"))
    )
    (net (code "49") (name "Net-(U1-PB7(XTAL2{slash}TOSC2))") (class "Default")
      (node (ref "C53") (pin "1") (pinfunction "1_1") (pintype "passive"))
      (node (ref "R52") (pin "1") (pinfunction "1_1") (pintype "passive"))
      (node (ref "U1") (pin "8") (pinfunction "PB7(XTAL2/TOSC2)_8") (pintype "bidirectional"))
      (node (ref "Y1") (pin "1") (pinfunction "1_1") (pintype "passive"))
    )
    (net (code "50") (name "Net-(U1-PC0(ADC0))") (class "Default")
      (node (ref "B1") (pin "A0") (pinfunction "A0_A0") (pintype "bidirectional"))
      (node (ref "U1") (pin "23") (pinfunction "PC0(ADC0)_23") (pintype "bidirectional"))
    )
    (net (code "51") (name "Net-(U1-PC1(ADC1))") (class "Default")
      (node (ref "B1") (pin "A1") (pinfunction "A1_A1") (pintype "bidirectional"))
      (node (ref "U1") (pin "24") (pinfunction "PC1(ADC1)_24") (pintype "bidirectional"))
    )
    (net (code "52") (name "Net-(U1-PC2(ADC2))") (class "Default")
      (node (ref "B1") (pin "A2") (pinfunction "A2_A2") (pintype "bidirectional"))
      (node (ref "U1") (pin "25") (pinfunction "PC2(ADC2)_25") (pintype "bidirectional"))
    )
    (net (code "53") (name "Net-(U1-PC3(ADC3))") (class "Default")
      (node (ref "B1") (pin "A3") (pinfunction "A3_A3") (pintype "bidirectional"))
      (node (ref "U1") (pin "26") (pinfunction "PC3(ADC3)_26") (pintype "bidirectional"))
    )
    (net (code "54") (name "Net-(U2-CELL)") (class "Default")
      (node (ref "R40") (pin "1") (pinfunction "1_1") (pintype "passive"))
      (node (ref "U2") (pin "2") (pinfunction "CELL_2") (pintype "bidirectional"))
    )
    (net (code "55") (name "Net-(U2-SCL)") (class "Default")
      (node (ref "JP1") (pin "3") (pinfunction "3_3") (pintype "passive"))
      (node (ref "U2") (pin "7") (pinfunction "SCL_7") (pintype "bidirectional"))
    )
    (net (code "56") (name "Net-(U2-SDA)") (class "Default")
      (node (ref "JP1") (pin "1") (pinfunction "1_1") (pintype "passive"))
      (node (ref "U2") (pin "8") (pinfunction "SDA_8") (pintype "bidirectional"))
    )
    (net (code "57") (name "Net-(U2-VDD)") (class "Default")
      (node (ref "C40") (pin "1") (pinfunction "1_1") (pintype "passive"))
      (node (ref "R41") (pin "1") (pinfunction "1_1") (pintype "passive"))
      (node (ref "U2") (pin "3") (pinfunction "VDD_3") (pintype "bidirectional"))
    )
    (net (code "58") (name "PACK+") (class "Default")
      (node (ref "BAT+") (pin "1") (pinfunction "1_1") (pintype "passive"))
      (node (ref "C1") (pin "2") (pinfunction "2_2") (pintype "passive"))
      (node (ref "C41") (pin "2") (pinfunction "2_2") (pintype "passive"))
      (node (ref "IC1") (pin "5") (pinfunction "BAT_5") (pintype "bidirectional"))
      (node (ref "R40") (pin "2") (pinfunction "2_2") (pintype "passive"))
      (node (ref "R41") (pin "2") (pinfunction "2_2") (pintype "passive"))
      (node (ref "S2") (pin "2") (pinfunction "P_2") (pintype "passive"))
    )
    (net (code "59") (name "RST") (class "Default")
      (node (ref "B1") (pin "RESET@1") (pinfunction "~{RESET}_RESET@1") (pintype "bidirectional"))
      (node (ref "B1") (pin "RESET@2") (pinfunction "~{RESET}_RESET@2") (pintype "bidirectional"))
      (node (ref "C60") (pin "1") (pinfunction "1_1") (pintype "passive"))
      (node (ref "D5") (pin "A") (pinfunction "A_A") (pintype "passive"))
      (node (ref "R51") (pin "2") (pinfunction "2_2") (pintype "passive"))
      (node (ref "S1") (pin "1") (pinfunction "1_1") (pintype "passive"))
      (node (ref "U1") (pin "29") (pinfunction "PC6(/RESET)_29") (pintype "bidirectional"))
    )
    (net (code "60") (name "RX") (class "Default")
      (node (ref "D3") (pin "C") (pinfunction "C_C") (pintype "passive"))
      (node (ref "R60") (pin "1") (pinfunction "1_1") (pintype "passive"))
      (node (ref "U$1") (pin "3") (pinfunction "RX_3") (pintype "bidirectional"))
    )
    (net (code "61") (name "RXD") (class "Default")
      (node (ref "B1") (pin "D0") (pinfunction "D0_D0") (pintype "bidirectional"))
      (node (ref "R61") (pin "2") (pinfunction "2_2") (pintype "passive"))
      (node (ref "U1") (pin "30") (pinfunction "PD0(RXD)_30") (pintype "bidirectional"))
    )
    (net (code "62") (name "SCK") (class "Default")
      (node (ref "B1") (pin "D13") (pinfunction "D13_D13") (pintype "bidirectional"))
      (node (ref "B1") (pin "SCK") (pinfunction "SCK_SCK") (pintype "bidirectional"))
      (node (ref "R81") (pin "1") (pinfunction "1_1") (pintype "passive"))
      (node (ref "U1") (pin "17") (pinfunction "PB5(SCK)_17") (pintype "bidirectional"))
    )
    (net (code "63") (name "SCL") (class "Default")
      (node (ref "B1") (pin "A5") (pinfunction "A5_A5") (pintype "bidirectional"))
      (node (ref "B1") (pin "SCL") (pinfunction "SCL_SCL") (pintype "bidirectional"))
      (node (ref "J1") (pin "3") (pinfunction "3_3") (pintype "passive"))
      (node (ref "JP1") (pin "4") (pinfunction "4_4") (pintype "passive"))
      (node (ref "U1") (pin "28") (pinfunction "PC5(ADC5/SCL)_28") (pintype "bidirectional"))
    )
    (net (code "64") (name "SDA") (class "Default")
      (node (ref "B1") (pin "A4") (pinfunction "A4_A4") (pintype "bidirectional"))
      (node (ref "B1") (pin "SDA") (pinfunction "SDA_SDA") (pintype "bidirectional"))
      (node (ref "J1") (pin "4") (pinfunction "4_4") (pintype "passive"))
      (node (ref "JP1") (pin "2") (pinfunction "2_2") (pintype "passive"))
      (node (ref "U1") (pin "27") (pinfunction "PC4(ADC4/SDA)_27") (pintype "bidirectional"))
    )
    (net (code "65") (name "TX") (class "Default")
      (node (ref "D4") (pin "C") (pinfunction "C_C") (pintype "passive"))
      (node (ref "R61") (pin "1") (pinfunction "1_1") (pintype "passive"))
      (node (ref "U$1") (pin "2") (pinfunction "TX_2") (pintype "bidirectional"))
    )
    (net (code "66") (name "TXD") (class "Default")
      (node (ref "B1") (pin "D1") (pinfunction "D1_D1") (pintype "bidirectional"))
      (node (ref "R60") (pin "2") (pinfunction "2_2") (pintype "passive"))
      (node (ref "U1") (pin "31") (pinfunction "PD1(TXD)_31") (pintype "bidirectional"))
    )
    (net (code "67") (name "unconnected-(B1-PadVIN)") (class "Default")
      (node (ref "B1") (pin "VIN") (pinfunction "VIN_VIN") (pintype "bidirectional"))
    )
    (net (code "68") (name "unconnected-(S2-S-Pad3)") (class "Default")
      (node (ref "S2") (pin "3") (pinfunction "S_3") (pintype "passive"))
    )
    (net (code "69") (name "unconnected-(U$1-CTS-Pad9)") (class "Default")
      (node (ref "U$1") (pin "9") (pinfunction "CTS_9") (pintype "bidirectional"))
    )
    (net (code "70") (name "unconnected-(U$1-DCD-Pad12)") (class "Default")
      (node (ref "U$1") (pin "12") (pinfunction "DCD_12") (pintype "bidirectional"))
    )
    (net (code "71") (name "unconnected-(U$1-DSR-Pad10)") (class "Default")
      (node (ref "U$1") (pin "10") (pinfunction "DSR_10") (pintype "bidirectional"))
    )
    (net (code "72") (name "unconnected-(U$1-RI-Pad11)") (class "Default")
      (node (ref "U$1") (pin "11") (pinfunction "RI_11") (pintype "bidirectional"))
    )
    (net (code "73") (name "unconnected-(U$1-RS232-Pad15)") (class "Default")
      (node (ref "U$1") (pin "15") (pinfunction "RS232_15") (pintype "bidirectional"))
    )
    (net (code "74") (name "unconnected-(U$1-RTS-Pad14)") (class "Default")
      (node (ref "U$1") (pin "14") (pinfunction "RTS_14") (pintype "bidirectional"))
    )
    (net (code "75") (name "unconnected-(U1-ADC6-Pad19)") (class "Default")
      (node (ref "U1") (pin "19") (pinfunction "ADC6_19") (pintype "bidirectional"))
    )
    (net (code "76") (name "unconnected-(U1-ADC7-Pad22)") (class "Default")
      (node (ref "U1") (pin "22") (pinfunction "ADC7_22") (pintype "bidirectional"))
    )
    (net (code "77") (name "unconnected-(U2-ALT-Pad5)") (class "Default")
      (node (ref "U2") (pin "5") (pinfunction "ALT_5") (pintype "bidirectional"))
    )
  )
)
